# High_Current_LED_Driver.net
KiCad netlist of a schematic drawn in Altium Designer
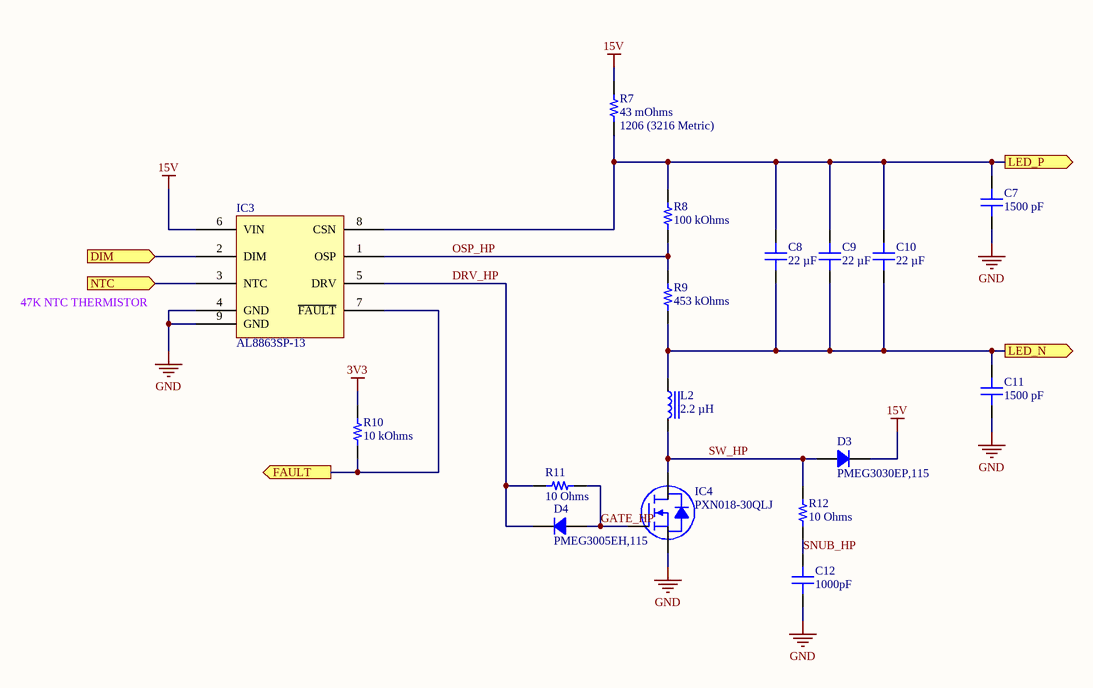
[diagram p0: High Current LED Driver.SchDoc]

(export (version "E")
  (design (tool "Eeschema 10.0.6"))
  (components
    (comp (ref "C7")
      (value "1500 pF")
      (footprint "CAP 0603_1608")
      (description "CAP CER 1500PF 50V C0G/NP0 0603")
      (fields
        (field (name "PART NUMBER") "0603N152J500CT")
        (field (name "MANUFACTURER") "Walsin Technology Corporation")
      )
      (libsource (lib "altiumlibrary.com") (part "Capacitor"))
    )
    (comp (ref "C8")
      (value "22 µF")
      (footprint "CAP 1210_3225 - 1MM")
      (description "CAP CER 22UF 25V X5R 1210")
      (fields
        (field (name "PART NUMBER") "CL32A226KAJNNNE")
        (field (name "MANUFACTURER") "Samsung Electro-Mechanics")
      )
      (libsource (lib "altiumlibrary.com") (part "Capacitor"))
    )
    (comp (ref "C9")
      (value "22 µF")
      (footprint "CAP 1210_3225 - 1MM")
      (description "CAP CER 22UF 25V X5R 1210")
      (fields
        (field (name "PART NUMBER") "CL32A226KAJNNNE")
        (field (name "MANUFACTURER") "Samsung Electro-Mechanics")
      )
      (libsource (lib "altiumlibrary.com") (part "Capacitor"))
    )
    (comp (ref "C10")
      (value "22 µF")
      (footprint "CAP 1210_3225 - 1MM")
      (description "CAP CER 22UF 25V X5R 1210")
      (fields
        (field (name "PART NUMBER") "CL32A226KAJNNNE")
        (field (name "MANUFACTURER") "Samsung Electro-Mechanics")
      )
      (libsource (lib "altiumlibrary.com") (part "Capacitor"))
    )
    (comp (ref "C11")
      (value "1500 pF")
      (footprint "CAP 0603_1608")
      (description "CAP CER 1500PF 50V C0G/NP0 0603")
      (fields
        (field (name "PART NUMBER") "0603N152J500CT")
        (field (name "MANUFACTURER") "Walsin Technology Corporation")
      )
      (libsource (lib "altiumlibrary.com") (part "Capacitor"))
    )
    (comp (ref "C12")
      (value "1000pF")
      (footprint "CAP 0603_1608")
      (description "CAP CER 1000PF 50V X7R 0603")
      (fields (field (name "PART NUMBER") "06035C102KAT2A") (field (name "MANUFACTURER") "AVX Corporation"))
      (libsource (lib "altiumlibrary.com") (part "Capacitor"))
    )
    (comp (ref "D3")
      (value "PMEG3030EP,115")
      (footprint "NEXPERIA SOD-128 CFP5")
      (description "DIODE SCHOTTKY 30V 3A CFP5")
      (fields (field (name "MANUFACTURER") "Nexperia USA Inc."))
      (libsource (lib "altiumlibrary.com") (part "Diode"))
    )
    (comp (ref "D4")
      (value "PMEG3005EH,115")
      (footprint "SOD123F")
      (description "DIODE SCHOTTKY 30V 500MA SOD123F")
      (fields (field (name "MANUFACTURER") "Nexperia USA Inc."))
      (libsource (lib "altiumlibrary.com") (part "Diode"))
    )
    (comp (ref "IC3")
      (value "AL8863SP-13")
      (footprint "DIODES INC SO-8EP")
      (description "LED MV INT SWITCH SO-8EP")
      (fields (field (name "MANUFACTURER") "Diodes Incorporated"))
      (libsource (lib "altiumlibrary.com") (part "DIODES INC AL8863"))
    )
    (comp (ref "IC4")
      (value "PXN018-30QLJ")
      (footprint "NEXPERIA MLPAK33 SOT8002-1")
      (description "PXN018-30QL/SOT8002/MLPAK33")
      (fields (field (name "MANUFACTURER") "Nexperia USA Inc."))
      (libsource (lib "altiumlibrary.com") (part "NEXPERIA PXN MLPAK33 MOSFET N-CH"))
    )
    (comp (ref "L2")
      (value "2.2 µH")
      (footprint "TAIYO YUDEN NRS8030")
      (description "FIXED IND 2.2UH 4.8A 19.5MOHM SM")
      (fields (field (name "PART NUMBER") "NRS8030T2R2NJGJ") (field (name "MANUFACTURER") "Taiyo Yuden"))
      (libsource (lib "altiumlibrary.com") (part "Inductor"))
    )
    (comp (ref "R7")
      (value "43 mOhms")
      (footprint "STACKPOLE CSR1206")
      (description "RES 0.043 OHM 5% 1/2W 1206")
      (fields
        (field (name "PART NUMBER") "RLP73M2BR043JTD")
        (field (name "PACKAGE / CASE") "1206 (3216 Metric)")
        (field (name "MANUFACTURER") "TE Connectivity Passive Product")
      )
      (libsource (lib "altiumlibrary.com") (part "Resistor"))
    )
    (comp (ref "R8")
      (value "100 kOhms")
      (footprint "RES 0603_1608")
      (description "RES 100K OHM 1% 1/10W 0603")
      (fields (field (name "PART NUMBER") "CRCW0603100KFKEAC") (field (name "MANUFACTURER") "Vishay Dale"))
      (libsource (lib "altiumlibrary.com") (part "Resistor"))
    )
    (comp (ref "R9")
      (value "453 kOhms")
      (footprint "RES 0603_1608")
      (description "RES 453K OHM 1% 1/10W 0603")
      (fields
        (field (name "PART NUMBER") "RMCF0603FT453K")
        (field (name "MANUFACTURER") "Stackpole Electronics Inc")
      )
      (libsource (lib "altiumlibrary.com") (part "Resistor"))
    )
    (comp (ref "R10")
      (value "10 kOhms")
      (footprint "RES 0603_1608")
      (description "RES SMD 10K OHM 5% 1/10W 0603")
      (fields
        (field (name "PART NUMBER") "ERJ-3GEYJ103V")
        (field (name "MANUFACTURER") "Panasonic Electronic Components")
      )
      (libsource (lib "altiumlibrary.com") (part "Resistor"))
    )
    (comp (ref "R11")
      (value "10 Ohms")
      (footprint "RES 0805_2012")
      (description "RES 10 OHM 5% 1/8W 0805")
      (fields (field (name "PART NUMBER") "CRCW080510R0JNEAC") (field (name "MANUFACTURER") "Vishay Dale"))
      (libsource (lib "altiumlibrary.com") (part "Resistor"))
    )
    (comp (ref "R12")
      (value "10 Ohms")
      (footprint "RES 0805_2012")
      (description "RES 10 OHM 5% 1/8W 0805")
      (fields (field (name "PART NUMBER") "CRCW080510R0JNEAC") (field (name "MANUFACTURER") "Vishay Dale"))
      (libsource (lib "altiumlibrary.com") (part "Resistor"))
    )
  )
  (nets
    (net (code "1") (name "/DIM") (class "Default")
      (node (ref "IC3") (pin "2") (pinfunction "DIM_2") (pintype "passive"))
    )
    (net (code "2") (name "/DRV_HP") (class "Default")
      (node (ref "D4") (pin "2") (pinfunction "2_2") (pintype "passive"))
      (node (ref "IC3") (pin "5") (pinfunction "DRV_5") (pintype "passive"))
      (node (ref "R11") (pin "1") (pinfunction "1_1") (pintype "passive"))
    )
    (net (code "3") (name "/FAULT") (class "Default")
      (node (ref "IC3") (pin "7") (pinfunction "~{FAULT}_7") (pintype "passive"))
      (node (ref "R10") (pin "1") (pinfunction "1_1") (pintype "passive"))
    )
    (net (code "4") (name "/GATE_HP") (class "Default")
      (node (ref "D4") (pin "1") (pinfunction "1_1") (pintype "passive"))
      (node (ref "IC4") (pin "G") (pinfunction "G_G") (pintype "passive"))
      (node (ref "R11") (pin "2") (pinfunction "2_2") (pintype "passive"))
    )
    (net (code "5") (name "/LED_N") (class "Default")
      (node (ref "C10") (pin "1") (pinfunction "1_1") (pintype "passive"))
      (node (ref "C11") (pin "2") (pinfunction "2_2") (pintype "passive"))
      (node (ref "C8") (pin "1") (pinfunction "1_1") (pintype "passive"))
      (node (ref "C9") (pin "1") (pinfunction "1_1") (pintype "passive"))
      (node (ref "L2") (pin "2") (pinfunction "2_2") (pintype "passive"))
      (node (ref "R9") (pin "1") (pinfunction "1_1") (pintype "passive"))
    )
    (net (code "6") (name "/LED_P") (class "Default")
      (node (ref "C10") (pin "2") (pinfunction "2_2") (pintype "passive"))
      (node (ref "C7") (pin "2") (pinfunction "2_2") (pintype "passive"))
      (node (ref "C8") (pin "2") (pinfunction "2_2") (pintype "passive"))
      (node (ref "C9") (pin "2") (pinfunction "2_2") (pintype "passive"))
      (node (ref "IC3") (pin "8") (pinfunction "CSN_8") (pintype "passive"))
      (node (ref "R7") (pin "1") (pinfunction "1_1") (pintype "passive"))
      (node (ref "R8") (pin "2") (pinfunction "2_2") (pintype "passive"))
    )
    (net (code "7") (name "/NTC") (class "Default")
      (node (ref "IC3") (pin "3") (pinfunction "NTC_3") (pintype "passive"))
    )
    (net (code "8") (name "/OSP_HP") (class "Default")
      (node (ref "IC3") (pin "1") (pinfunction "OSP_1") (pintype "passive"))
      (node (ref "R8") (pin "1") (pinfunction "1_1") (pintype "passive"))
      (node (ref "R9") (pin "2") (pinfunction "2_2") (pintype "passive"))
    )
    (net (code "9") (name "/SNUB_HP") (class "Default")
      (node (ref "C12") (pin "2") (pinfunction "2_2") (pintype "passive"))
      (node (ref "R12") (pin "1") (pinfunction "1_1") (pintype "passive"))
    )
    (net (code "10") (name "/SW_HP") (class "Default")
      (node (ref "D3") (pin "1") (pinfunction "1_1") (pintype "passive"))
      (node (ref "IC4") (pin "D") (pinfunction "D_D") (pintype "passive"))
      (node (ref "L2") (pin "1") (pinfunction "1_1") (pintype "passive"))
      (node (ref "R12") (pin "2") (pinfunction "2_2") (pintype "passive"))
    )
    (net (code "11") (name "3V3") (class "Default")
      (node (ref "R10") (pin "2") (pinfunction "2_2") (pintype "passive"))
    )
    (net (code "12") (name "15V") (class "Default")
      (node (ref "D3") (pin "2") (pinfunction "2_2") (pintype "passive"))
      (node (ref "IC3") (pin "6") (pinfunction "VIN_6") (pintype "passive"))
      (node (ref "R7") (pin "2") (pinfunction "2_2") (pintype "passive"))
    )
    (net (code "13") (name "GND") (class "Default")
      (node (ref "C11") (pin "1") (pinfunction "1_1") (pintype "passive"))
      (node (ref "C12") (pin "1") (pinfunction "1_1") (pintype "passive"))
      (node (ref "C7") (pin "1") (pinfunction "1_1") (pintype "passive"))
      (node (ref "IC3") (pin "4") (pinfunction "GND_4") (pintype "passive"))
      (node (ref "IC3") (pin "9") (pinfunction "GND_9") (pintype "passive"))
      (node (ref "IC4") (pin "S") (pinfunction "S_S") (pintype "passive"))
    )
  )
)
